# buderus_ems.net
KiCad netlist of a schematic drawn in EAGLE
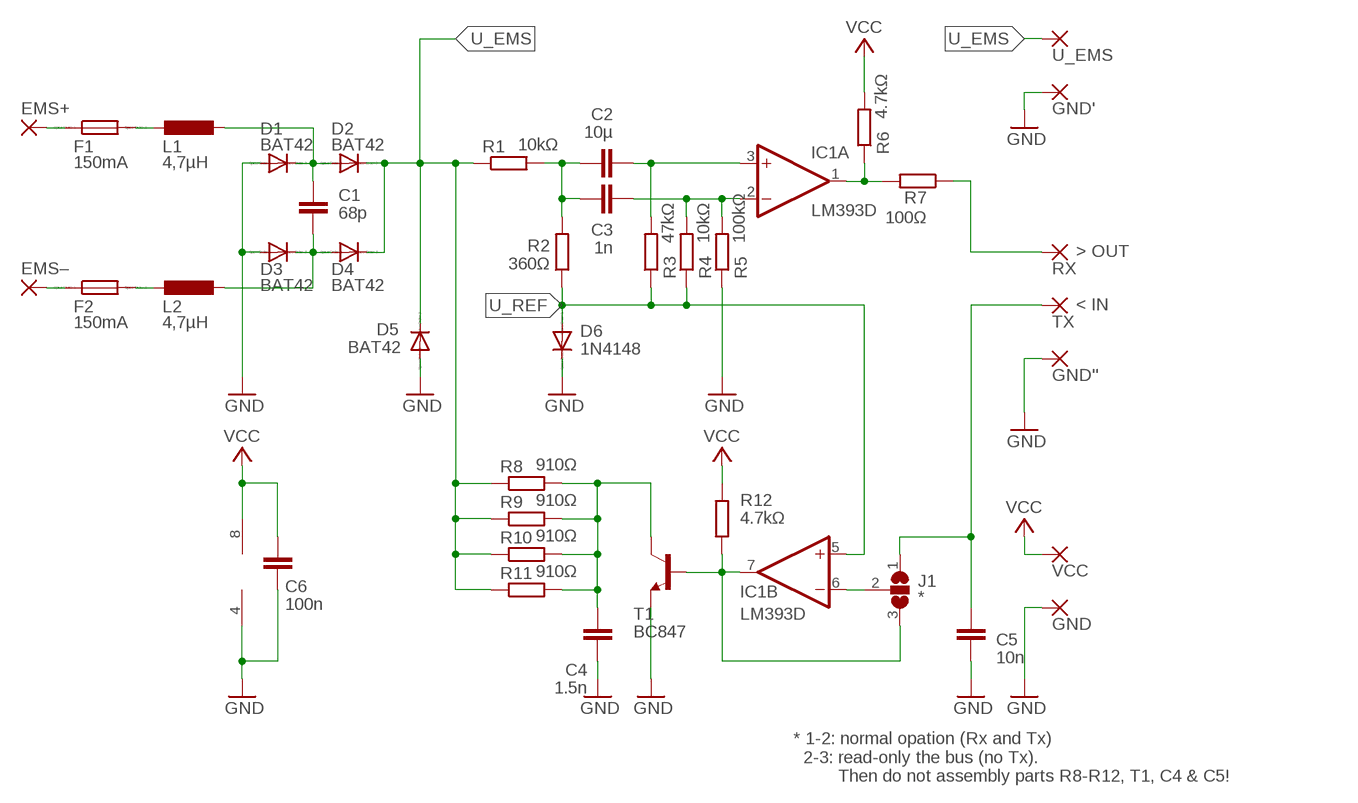
[diagram p0: schematic, sheet 1]

(export (version "E")
  (design (tool "Eeschema 10.0.6"))
  (components
    (comp (ref "C1")
      (value "68p")
      (footprint "eagle-import:C0603")
      (libsource (lib "eagle-import") (part "C-EUC0603"))
    )
    (comp (ref "C2")
      (value "10µ")
      (footprint "eagle-import:C0603")
      (libsource (lib "eagle-import") (part "C-EUC0603"))
    )
    (comp (ref "C3")
      (value "1n")
      (footprint "eagle-import:C0603")
      (libsource (lib "eagle-import") (part "C-EUC0603"))
    )
    (comp (ref "C4")
      (value "1.5n")
      (footprint "eagle-import:C0603")
      (libsource (lib "eagle-import") (part "C-EUC0603"))
    )
    (comp (ref "C5")
      (value "10n")
      (footprint "eagle-import:C0603")
      (libsource (lib "eagle-import") (part "C-EUC0603"))
    )
    (comp (ref "C6")
      (value "100n")
      (footprint "eagle-import:C0603")
      (libsource (lib "eagle-import") (part "C-EUC0603"))
    )
    (comp (ref "D1")
      (value "BAT42")
      (footprint "eagle-import:MINIMELF")
      (libsource (lib "eagle-import") (part "DIODE-MINIMELF"))
    )
    (comp (ref "D2")
      (value "BAT42")
      (footprint "eagle-import:MINIMELF")
      (libsource (lib "eagle-import") (part "DIODE-MINIMELF"))
    )
    (comp (ref "D3")
      (value "BAT42")
      (footprint "eagle-import:MINIMELF")
      (libsource (lib "eagle-import") (part "DIODE-MINIMELF"))
    )
    (comp (ref "D4")
      (value "BAT42")
      (footprint "eagle-import:MINIMELF")
      (libsource (lib "eagle-import") (part "DIODE-MINIMELF"))
    )
    (comp (ref "D5")
      (value "BAT42")
      (footprint "eagle-import:MINIMELF")
      (libsource (lib "eagle-import") (part "DIODE-MINIMELF"))
    )
    (comp (ref "D6")
      (value "1N4148")
      (footprint "eagle-import:MINIMELF")
      (libsource (lib "eagle-import") (part "DIODE-MINIMELF"))
    )
    (comp (ref "EMS+")
      (value "WIREPAD2,15/1,0")
      (footprint "eagle-import:2,15_1,0")
      (libsource (lib "eagle-import") (part "WIREPAD2,15/1,0"))
    )
    (comp (ref "EMS‒")
      (value "WIREPAD2,15/1,0")
      (footprint "eagle-import:2,15_1,0")
      (libsource (lib "eagle-import") (part "WIREPAD2,15/1,0"))
    )
    (comp (ref "F1")
      (value "150mA")
      (footprint "eagle-import:R1210")
      (libsource (lib "eagle-import") (part "RR1210"))
    )
    (comp (ref "F2")
      (value "150mA")
      (footprint "eagle-import:R1210")
      (libsource (lib "eagle-import") (part "RR1210"))
    )
    (comp (ref "GND")
      (value "WIREPAD2,15/1,0")
      (footprint "eagle-import:2,15_1,0")
      (libsource (lib "eagle-import") (part "WIREPAD2,15/1,0"))
    )
    (comp (ref "GND'")
      (value "WIREPAD2,15/1,0")
      (footprint "eagle-import:2,15_1,0")
      (libsource (lib "eagle-import") (part "WIREPAD2,15/1,0"))
    )
    (comp (ref "GND''")
      (value "WIREPAD2,15/1,0")
      (footprint "eagle-import:2,15_1,0")
      (libsource (lib "eagle-import") (part "WIREPAD2,15/1,0"))
    )
    (comp (ref "IC1")
      (value "LM393D")
      (footprint "eagle-import:SO08")
      (libsource (lib "eagle-import") (part "LM393D"))
    )
    (comp (ref "J1")
      (value "*")
      (footprint "eagle-import:SJ_2")
      (libsource (lib "eagle-import") (part "SJ2W"))
    )
    (comp (ref "L1")
      (value "4,7µH")
      (footprint "eagle-import:L3216C")
      (libsource (lib "eagle-import") (part "L-EUL3216C"))
    )
    (comp (ref "L2")
      (value "4,7µH")
      (footprint "eagle-import:L3216C")
      (libsource (lib "eagle-import") (part "L-EUL3216C"))
    )
    (comp (ref "R1")
      (value "10kΩ")
      (footprint "eagle-import:R0805")
      (libsource (lib "eagle-import") (part "R-EU_R0805"))
    )
    (comp (ref "R2")
      (value "360Ω")
      (footprint "eagle-import:R0805")
      (libsource (lib "eagle-import") (part "R-EU_R0805"))
    )
    (comp (ref "R3")
      (value "47kΩ")
      (footprint "eagle-import:R0805")
      (libsource (lib "eagle-import") (part "R-EU_R0805"))
    )
    (comp (ref "R4")
      (value "10kΩ")
      (footprint "eagle-import:R0805")
      (libsource (lib "eagle-import") (part "R-EU_R0805"))
    )
    (comp (ref "R5")
      (value "100kΩ")
      (footprint "eagle-import:R0805")
      (libsource (lib "eagle-import") (part "R-EU_R0805"))
    )
    (comp (ref "R6")
      (value "4.7kΩ")
      (footprint "eagle-import:R0805")
      (libsource (lib "eagle-import") (part "R-EU_R0805"))
    )
    (comp (ref "R7")
      (value "100Ω")
      (footprint "eagle-import:R0805")
      (libsource (lib "eagle-import") (part "R-EU_R0805"))
    )
    (comp (ref "R8")
      (value "910Ω")
      (footprint "eagle-import:R0805")
      (libsource (lib "eagle-import") (part "R-EU_R0805"))
    )
    (comp (ref "R9")
      (value "910Ω")
      (footprint "eagle-import:R0805")
      (libsource (lib "eagle-import") (part "R-EU_R0805"))
    )
    (comp (ref "R10")
      (value "910Ω")
      (footprint "eagle-import:R0805")
      (libsource (lib "eagle-import") (part "R-EU_R0805"))
    )
    (comp (ref "R11")
      (value "910Ω")
      (footprint "eagle-import:R0805")
      (libsource (lib "eagle-import") (part "R-EU_R0805"))
    )
    (comp (ref "R12")
      (value "4.7kΩ")
      (footprint "eagle-import:R0805")
      (libsource (lib "eagle-import") (part "R-EU_R0805"))
    )
    (comp (ref "RX")
      (value "WIREPAD2,15/1,0")
      (footprint "eagle-import:2,15_1,0")
      (libsource (lib "eagle-import") (part "WIREPAD2,15/1,0"))
    )
    (comp (ref "T1")
      (value "BC847")
      (footprint "eagle-import:SOT23")
      (libsource (lib "eagle-import") (part "BC847"))
    )
    (comp (ref "TX")
      (value "WIREPAD2,15/1,0")
      (footprint "eagle-import:2,15_1,0")
      (libsource (lib "eagle-import") (part "WIREPAD2,15/1,0"))
    )
    (comp (ref "U_EMS")
      (value "WIREPAD2,15/1,0")
      (footprint "eagle-import:2,15_1,0")
      (libsource (lib "eagle-import") (part "WIREPAD2,15/1,0"))
    )
    (comp (ref "VCC")
      (value "WIREPAD2,15/1,0")
      (footprint "eagle-import:2,15_1,0")
      (libsource (lib "eagle-import") (part "WIREPAD2,15/1,0"))
    )
  )
  (nets
    (net (code "1") (name "GND") (class "Default")
      (node (ref "C4") (pin "1") (pinfunction "1_1") (pintype "passive"))
      (node (ref "C5") (pin "1") (pinfunction "1_1") (pintype "passive"))
      (node (ref "C6") (pin "1") (pinfunction "1_1") (pintype "passive"))
      (node (ref "D1") (pin "A") (pinfunction "A_A") (pintype "passive"))
      (node (ref "D3") (pin "A") (pinfunction "A_A") (pintype "passive"))
      (node (ref "D5") (pin "A") (pinfunction "A_A") (pintype "passive"))
      (node (ref "D6") (pin "C") (pinfunction "C_C") (pintype "passive"))
      (node (ref "GND") (pin "1") (pinfunction "P_1") (pintype "passive"))
      (node (ref "GND'") (pin "1") (pinfunction "P_1") (pintype "passive"))
      (node (ref "GND''") (pin "1") (pinfunction "P_1") (pintype "passive"))
      (node (ref "IC1") (pin "4") (pinfunction "V-_4") (pintype "power_in"))
      (node (ref "R5") (pin "1") (pinfunction "1_1") (pintype "passive"))
      (node (ref "T1") (pin "2") (pinfunction "E_2") (pintype "passive"))
    )
    (net (code "2") (name "Net-(C1-Pad1)") (class "Default")
      (node (ref "C1") (pin "1") (pinfunction "1_1") (pintype "passive"))
      (node (ref "D3") (pin "C") (pinfunction "C_C") (pintype "passive"))
      (node (ref "D4") (pin "A") (pinfunction "A_A") (pintype "passive"))
      (node (ref "L2") (pin "2") (pinfunction "2_2") (pintype "passive"))
    )
    (net (code "3") (name "Net-(C1-Pad2)") (class "Default")
      (node (ref "C1") (pin "2") (pinfunction "2_2") (pintype "passive"))
      (node (ref "D1") (pin "C") (pinfunction "C_C") (pintype "passive"))
      (node (ref "D2") (pin "A") (pinfunction "A_A") (pintype "passive"))
      (node (ref "L1") (pin "2") (pinfunction "2_2") (pintype "passive"))
    )
    (net (code "4") (name "Net-(C2-Pad1)") (class "Default")
      (node (ref "C2") (pin "1") (pinfunction "1_1") (pintype "passive"))
      (node (ref "C3") (pin "1") (pinfunction "1_1") (pintype "passive"))
      (node (ref "R1") (pin "2") (pinfunction "2_2") (pintype "passive"))
      (node (ref "R2") (pin "2") (pinfunction "2_2") (pintype "passive"))
    )
    (net (code "5") (name "Net-(EMS+-P)") (class "Default")
      (node (ref "EMS+") (pin "1") (pinfunction "P_1") (pintype "passive"))
      (node (ref "F1") (pin "1") (pinfunction "1_1") (pintype "passive"))
    )
    (net (code "6") (name "Net-(EMS‒-P)") (class "Default")
      (node (ref "EMS‒") (pin "1") (pinfunction "P_1") (pintype "passive"))
      (node (ref "F2") (pin "1") (pinfunction "1_1") (pintype "passive"))
    )
    (net (code "7") (name "Net-(F1-Pad2)") (class "Default")
      (node (ref "F1") (pin "2") (pinfunction "2_2") (pintype "passive"))
      (node (ref "L1") (pin "1") (pinfunction "1_1") (pintype "passive"))
    )
    (net (code "8") (name "Net-(F2-Pad2)") (class "Default")
      (node (ref "F2") (pin "2") (pinfunction "2_2") (pintype "passive"))
      (node (ref "L2") (pin "1") (pinfunction "1_1") (pintype "passive"))
    )
    (net (code "9") (name "Net-(IC1A-+IN)") (class "Default")
      (node (ref "C2") (pin "2") (pinfunction "2_2") (pintype "passive"))
      (node (ref "IC1") (pin "3") (pinfunction "+IN_3") (pintype "input"))
      (node (ref "R3") (pin "2") (pinfunction "2_2") (pintype "passive"))
    )
    (net (code "10") (name "Net-(IC1A--IN)") (class "Default")
      (node (ref "C3") (pin "2") (pinfunction "2_2") (pintype "passive"))
      (node (ref "IC1") (pin "2") (pinfunction "-IN_2") (pintype "input"))
      (node (ref "R4") (pin "2") (pinfunction "2_2") (pintype "passive"))
      (node (ref "R5") (pin "2") (pinfunction "2_2") (pintype "passive"))
    )
    (net (code "11") (name "Net-(IC1A-OUT)") (class "Default")
      (node (ref "IC1") (pin "1") (pinfunction "OUT_1") (pintype "output"))
      (node (ref "R6") (pin "1") (pinfunction "1_1") (pintype "passive"))
      (node (ref "R7") (pin "2") (pinfunction "2_2") (pintype "passive"))
    )
    (net (code "12") (name "Net-(IC1B--IN)") (class "Default")
      (node (ref "IC1") (pin "6") (pinfunction "-IN_6") (pintype "input"))
      (node (ref "J1") (pin "2") (pinfunction "2_2") (pintype "passive"))
    )
    (net (code "13") (name "Net-(IC1B-OUT)") (class "Default")
      (node (ref "IC1") (pin "7") (pinfunction "OUT_7") (pintype "output"))
      (node (ref "J1") (pin "3") (pinfunction "3_3") (pintype "passive"))
      (node (ref "R12") (pin "1") (pinfunction "1_1") (pintype "passive"))
      (node (ref "T1") (pin "1") (pinfunction "B_1") (pintype "passive"))
    )
    (net (code "14") (name "Net-(RX-P)") (class "Default")
      (node (ref "R7") (pin "1") (pinfunction "1_1") (pintype "passive"))
      (node (ref "RX") (pin "1") (pinfunction "P_1") (pintype "passive"))
    )
    (net (code "15") (name "Net-(T1-C)") (class "Default")
      (node (ref "C4") (pin "2") (pinfunction "2_2") (pintype "passive"))
      (node (ref "R10") (pin "2") (pinfunction "2_2") (pintype "passive"))
      (node (ref "R11") (pin "2") (pinfunction "2_2") (pintype "passive"))
      (node (ref "R8") (pin "2") (pinfunction "2_2") (pintype "passive"))
      (node (ref "R9") (pin "2") (pinfunction "2_2") (pintype "passive"))
      (node (ref "T1") (pin "3") (pinfunction "C_3") (pintype "passive"))
    )
    (net (code "16") (name "Net-(TX-P)") (class "Default")
      (node (ref "C5") (pin "2") (pinfunction "2_2") (pintype "passive"))
      (node (ref "J1") (pin "1") (pinfunction "1_1") (pintype "passive"))
      (node (ref "TX") (pin "1") (pinfunction "P_1") (pintype "passive"))
    )
    (net (code "17") (name "U_EMS") (class "Default")
      (node (ref "D2") (pin "C") (pinfunction "C_C") (pintype "passive"))
      (node (ref "D4") (pin "C") (pinfunction "C_C") (pintype "passive"))
      (node (ref "D5") (pin "C") (pinfunction "C_C") (pintype "passive"))
      (node (ref "R1") (pin "1") (pinfunction "1_1") (pintype "passive"))
      (node (ref "R10") (pin "1") (pinfunction "1_1") (pintype "passive"))
      (node (ref "R11") (pin "1") (pinfunction "1_1") (pintype "passive"))
      (node (ref "R8") (pin "1") (pinfunction "1_1") (pintype "passive"))
      (node (ref "R9") (pin "1") (pinfunction "1_1") (pintype "passive"))
      (node (ref "U_EMS") (pin "1") (pinfunction "P_1") (pintype "passive"))
    )
    (net (code "18") (name "U_REF") (class "Default")
      (node (ref "D6") (pin "A") (pinfunction "A_A") (pintype "passive"))
      (node (ref "IC1") (pin "5") (pinfunction "+IN_5") (pintype "input"))
      (node (ref "R2") (pin "1") (pinfunction "1_1") (pintype "passive"))
      (node (ref "R3") (pin "1") (pinfunction "1_1") (pintype "passive"))
      (node (ref "R4") (pin "1") (pinfunction "1_1") (pintype "passive"))
    )
    (net (code "19") (name "VCC") (class "Default")
      (node (ref "C6") (pin "2") (pinfunction "2_2") (pintype "passive"))
      (node (ref "IC1") (pin "8") (pinfunction "V+_8") (pintype "power_in"))
      (node (ref "R12") (pin "2") (pinfunction "2_2") (pintype "passive"))
      (node (ref "R6") (pin "2") (pinfunction "2_2") (pintype "passive"))
      (node (ref "VCC") (pin "1") (pinfunction "P_1") (pintype "passive"))
    )
  )
)
